# nixie_2020_mainboard_v3_7digit.net
KiCad netlist of a schematic drawn in EAGLE
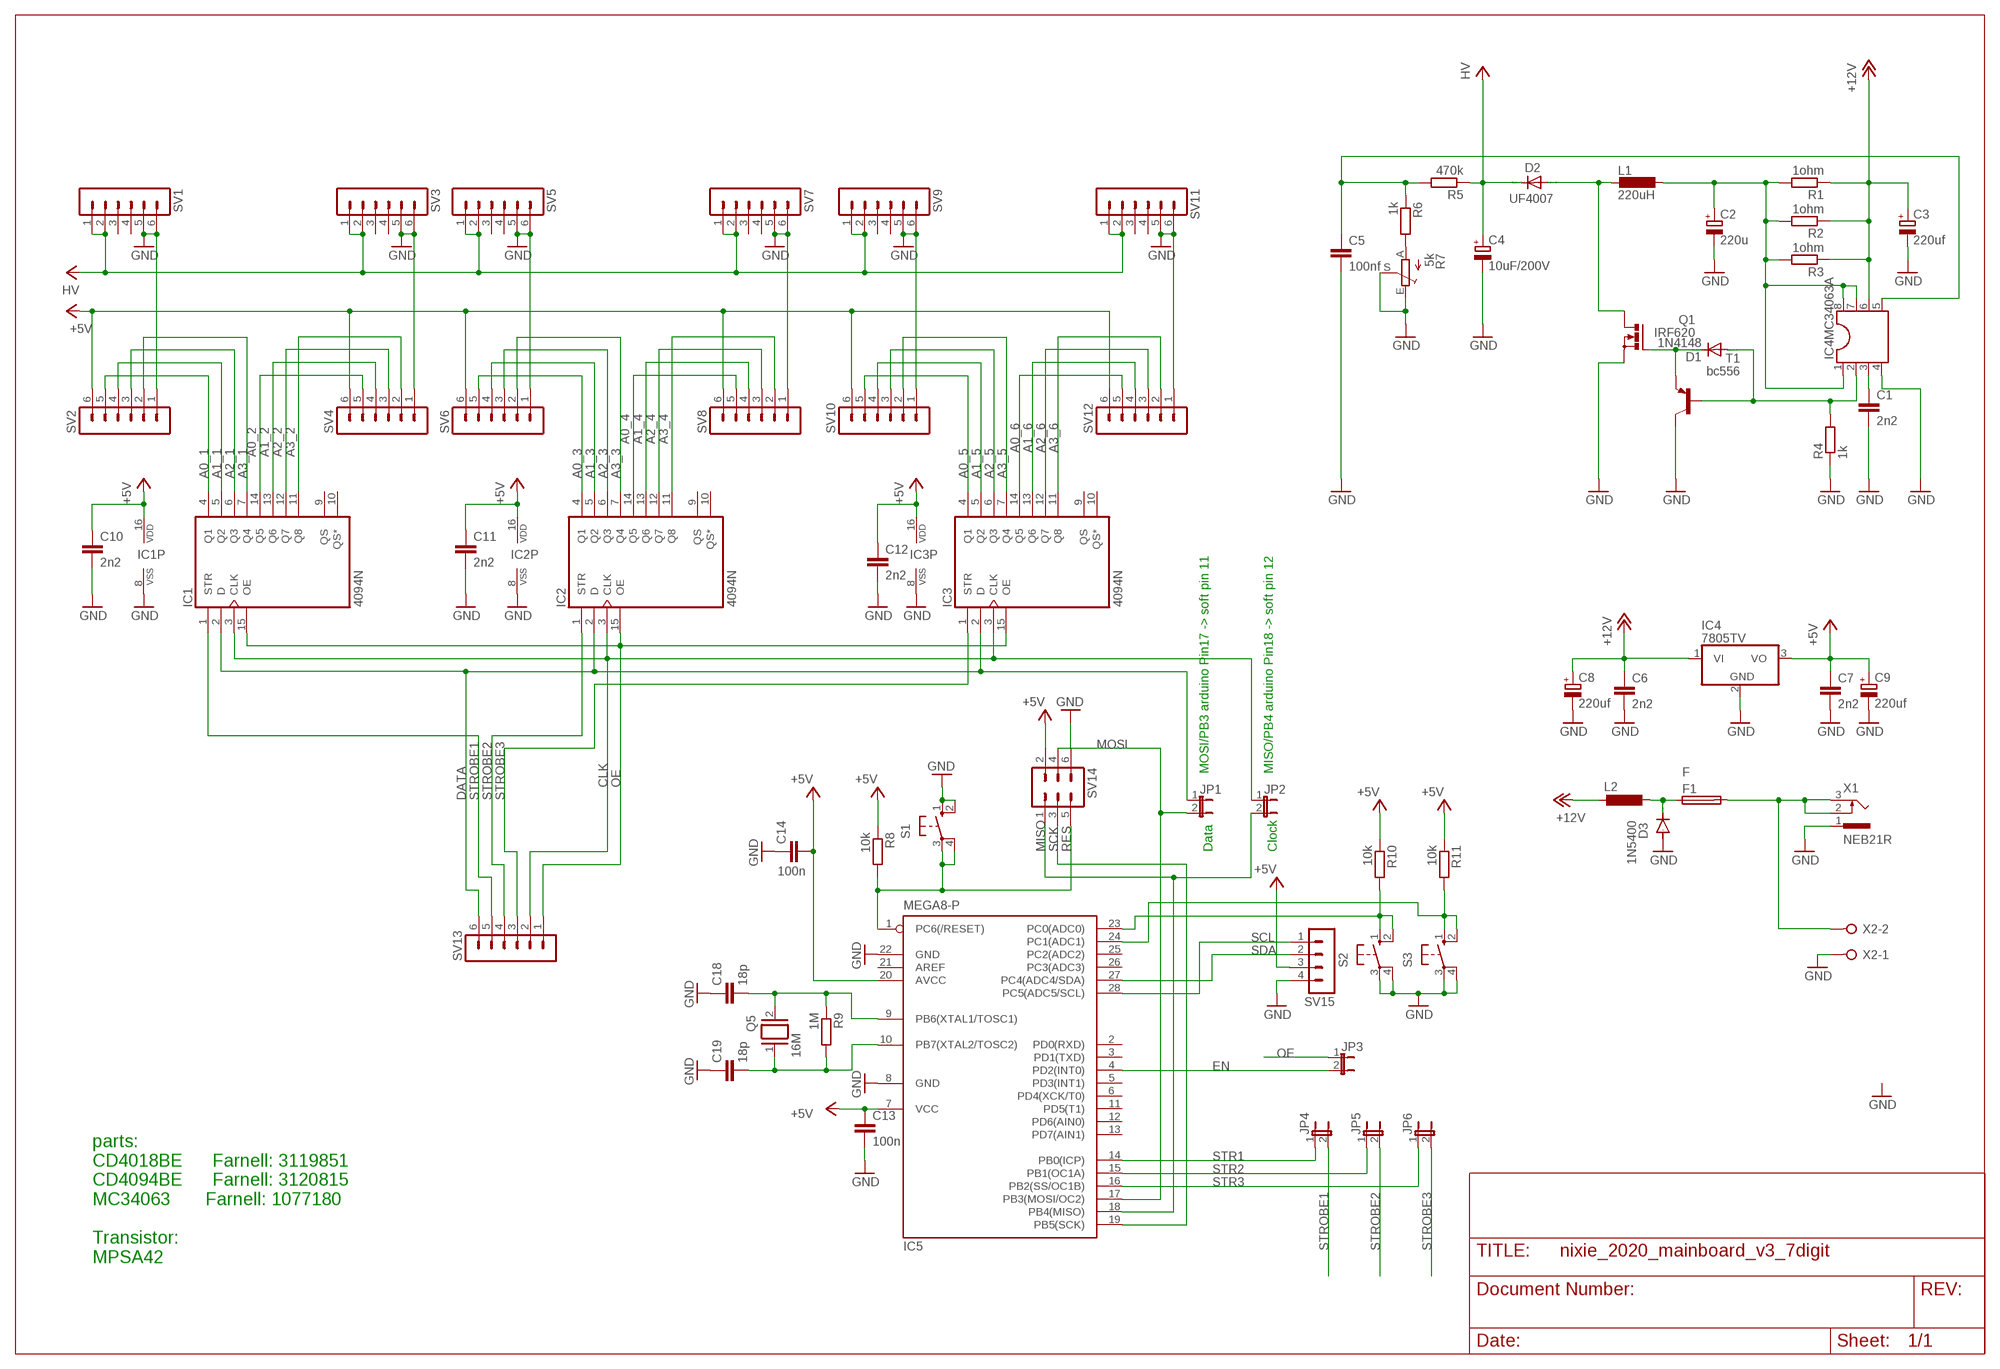
[diagram p0: schematic, sheet 1]

(export (version "E")
  (design (tool "Eeschema 10.0.6"))
  (components
    (comp (ref "C1")
      (value "2n2")
      (footprint "eagle-import:C050-030X075")
      (libsource (lib "eagle-import") (part "C-EU050-030X075"))
    )
    (comp (ref "C2")
      (value "220u")
      (footprint "eagle-import:E5-10,5")
      (libsource (lib "eagle-import") (part "CPOL-EUE5-10.5"))
    )
    (comp (ref "C3")
      (value "220uf")
      (footprint "eagle-import:E5-10,5")
      (libsource (lib "eagle-import") (part "CPOL-EUE5-10.5"))
    )
    (comp (ref "C4")
      (value "10uF/200V")
      (footprint "eagle-import:E5-10,5")
      (libsource (lib "eagle-import") (part "CPOL-EUE5-10.5"))
    )
    (comp (ref "C5")
      (value "100nf")
      (footprint "eagle-import:C075-042X103")
      (libsource (lib "eagle-import") (part "C-EU075-042X103"))
    )
    (comp (ref "C6")
      (value "2n2")
      (footprint "eagle-import:C050-030X075")
      (libsource (lib "eagle-import") (part "C-EU050-030X075"))
    )
    (comp (ref "C7")
      (value "2n2")
      (footprint "eagle-import:C050-030X075")
      (libsource (lib "eagle-import") (part "C-EU050-030X075"))
    )
    (comp (ref "C8")
      (value "220uf")
      (footprint "eagle-import:E5-10,5")
      (libsource (lib "eagle-import") (part "CPOL-EUE5-10.5"))
    )
    (comp (ref "C9")
      (value "220uf")
      (footprint "eagle-import:E5-10,5")
      (libsource (lib "eagle-import") (part "CPOL-EUE5-10.5"))
    )
    (comp (ref "C10")
      (value "2n2")
      (footprint "eagle-import:C050-030X075")
      (libsource (lib "eagle-import") (part "C-EU050-030X075"))
    )
    (comp (ref "C11")
      (value "2n2")
      (footprint "eagle-import:C050-030X075")
      (libsource (lib "eagle-import") (part "C-EU050-030X075"))
    )
    (comp (ref "C12")
      (value "2n2")
      (footprint "eagle-import:C050-030X075")
      (libsource (lib "eagle-import") (part "C-EU050-030X075"))
    )
    (comp (ref "C13")
      (value "100n")
      (footprint "eagle-import:C050-025X075")
      (libsource (lib "eagle-import") (part "resistor_C-EU050-025X075"))
    )
    (comp (ref "C14")
      (value "100n")
      (footprint "eagle-import:C050-025X075")
      (libsource (lib "eagle-import") (part "resistor_C-EU050-025X075"))
    )
    (comp (ref "C18")
      (value "18p")
      (footprint "eagle-import:C050-025X075")
      (libsource (lib "eagle-import") (part "resistor_C-EU050-025X075"))
    )
    (comp (ref "C19")
      (value "18p")
      (footprint "eagle-import:C050-025X075")
      (libsource (lib "eagle-import") (part "resistor_C-EU050-025X075"))
    )
    (comp (ref "D1")
      (value "1N4148")
      (footprint "eagle-import:DO35-10")
      (libsource (lib "eagle-import") (part "1N4148DO35-10"))
    )
    (comp (ref "D2")
      (value "UF4007")
      (footprint "eagle-import:DO35-10")
      (libsource (lib "eagle-import") (part "BAV21"))
    )
    (comp (ref "D3")
      (value "1N5400")
      (footprint "eagle-import:DO201-15")
      (libsource (lib "eagle-import") (part "1N5400"))
    )
    (comp (ref "F1")
      (value "F")
      (footprint "eagle-import:SHK20L")
      (libsource (lib "eagle-import") (part "FUSESHK20L"))
    )
    (comp (ref "IC1")
      (value "4094N")
      (footprint "eagle-import:DIL16")
      (libsource (lib "eagle-import") (part "4094N"))
    )
    (comp (ref "IC2")
      (value "4094N")
      (footprint "eagle-import:DIL16")
      (libsource (lib "eagle-import") (part "4094N"))
    )
    (comp (ref "IC3")
      (value "4094N")
      (footprint "eagle-import:DIL16")
      (libsource (lib "eagle-import") (part "4094N"))
    )
    (comp (ref "IC4")
      (value "7805TV")
      (footprint "eagle-import:TO220V")
      (libsource (lib "eagle-import") (part "78TV05"))
    )
    (comp (ref "IC4MC34063A")
      (value "DIL8S")
      (footprint "eagle-import:SOCKET-08")
      (libsource (lib "eagle-import") (part "DIL8S"))
    )
    (comp (ref "IC5")
      (value "MEGA8-P")
      (footprint "eagle-import:DIL28-3")
      (libsource (lib "eagle-import") (part "MEGA8-P"))
    )
    (comp (ref "JP1")
      (value "JP1E")
      (footprint "eagle-import:JP1")
      (libsource (lib "eagle-import") (part "JP1E"))
    )
    (comp (ref "JP2")
      (value "JP1E")
      (footprint "eagle-import:JP1")
      (libsource (lib "eagle-import") (part "JP1E"))
    )
    (comp (ref "JP3")
      (value "JP1E")
      (footprint "eagle-import:JP1")
      (libsource (lib "eagle-import") (part "JP1E"))
    )
    (comp (ref "JP4")
      (value "JP1E")
      (footprint "eagle-import:JP1")
      (libsource (lib "eagle-import") (part "JP1E"))
    )
    (comp (ref "JP5")
      (value "JP1E")
      (footprint "eagle-import:JP1")
      (libsource (lib "eagle-import") (part "JP1E"))
    )
    (comp (ref "JP6")
      (value "JP1E")
      (footprint "eagle-import:JP1")
      (libsource (lib "eagle-import") (part "JP1E"))
    )
    (comp (ref "L1")
      (value "220uH")
      (footprint "eagle-import:LAN02KR")
      (libsource (lib "eagle-import") (part "L-EULAN02KR"))
    )
    (comp (ref "L2")
      (value "L-EU0207/10")
      (footprint "eagle-import:0207_10")
      (libsource (lib "eagle-import") (part "rcl_334_L-EU0207/10"))
    )
    (comp (ref "Q1")
      (value "IRF620")
      (footprint "eagle-import:TO220BV")
      (libsource (lib "eagle-import") (part "IRF512"))
    )
    (comp (ref "Q5")
      (value "16M")
      (footprint "eagle-import:QS")
      (libsource (lib "eagle-import") (part "XTAL/S"))
    )
    (comp (ref "R1")
      (value "1ohm")
      (footprint "eagle-import:0207_12")
      (libsource (lib "eagle-import") (part "R-EU_0207/12"))
    )
    (comp (ref "R2")
      (value "1ohm")
      (footprint "eagle-import:0207_12")
      (libsource (lib "eagle-import") (part "R-EU_0207/12"))
    )
    (comp (ref "R3")
      (value "1ohm")
      (footprint "eagle-import:0207_12")
      (libsource (lib "eagle-import") (part "R-EU_0207/12"))
    )
    (comp (ref "R4")
      (value "1k")
      (footprint "eagle-import:0207_12")
      (libsource (lib "eagle-import") (part "R-EU_0207/12"))
    )
    (comp (ref "R5")
      (value "470k")
      (footprint "eagle-import:0207_12")
      (libsource (lib "eagle-import") (part "R-EU_0207/12"))
    )
    (comp (ref "R6")
      (value "1k")
      (footprint "eagle-import:0207_12")
      (libsource (lib "eagle-import") (part "R-EU_0207/12"))
    )
    (comp (ref "R7")
      (value "5k")
      (footprint "eagle-import:RJ9W")
      (libsource (lib "eagle-import") (part "TRIM_EU-RJ9W"))
    )
    (comp (ref "R8")
      (value "10k")
      (footprint "eagle-import:0207_12")
      (libsource (lib "eagle-import") (part "R-EU_0207/12"))
    )
    (comp (ref "R9")
      (value "1M")
      (footprint "eagle-import:0207_12")
      (libsource (lib "eagle-import") (part "R-EU_0207/12"))
    )
    (comp (ref "R10")
      (value "10k")
      (footprint "eagle-import:0207_12")
      (libsource (lib "eagle-import") (part "R-EU_0207/12"))
    )
    (comp (ref "R11")
      (value "10k")
      (footprint "eagle-import:0207_12")
      (libsource (lib "eagle-import") (part "R-EU_0207/12"))
    )
    (comp (ref "S1")
      (value "10-XX")
      (footprint "eagle-import:B3F-10XX")
      (fields (field (name "MPN") "B3F-1000"))
      (libsource (lib "eagle-import") (part "10-XX"))
    )
    (comp (ref "S2")
      (value "10-XX")
      (footprint "eagle-import:B3F-10XX")
      (fields (field (name "MPN") "B3F-1000"))
      (libsource (lib "eagle-import") (part "10-XX"))
    )
    (comp (ref "S3")
      (value "10-XX")
      (footprint "eagle-import:B3F-10XX")
      (fields (field (name "MPN") "B3F-1000"))
      (libsource (lib "eagle-import") (part "10-XX"))
    )
    (comp (ref "SV1")
      (value "MA06-1")
      (footprint "eagle-import:MA06-1")
      (libsource (lib "eagle-import") (part "MA06-1"))
    )
    (comp (ref "SV2")
      (value "MA06-1")
      (footprint "eagle-import:MA06-1")
      (libsource (lib "eagle-import") (part "MA06-1"))
    )
    (comp (ref "SV3")
      (value "MA06-1")
      (footprint "eagle-import:MA06-1")
      (libsource (lib "eagle-import") (part "MA06-1"))
    )
    (comp (ref "SV4")
      (value "MA06-1")
      (footprint "eagle-import:MA06-1")
      (libsource (lib "eagle-import") (part "MA06-1"))
    )
    (comp (ref "SV5")
      (value "MA06-1")
      (footprint "eagle-import:MA06-1")
      (libsource (lib "eagle-import") (part "MA06-1"))
    )
    (comp (ref "SV6")
      (value "MA06-1")
      (footprint "eagle-import:MA06-1")
      (libsource (lib "eagle-import") (part "MA06-1"))
    )
    (comp (ref "SV7")
      (value "MA06-1")
      (footprint "eagle-import:MA06-1")
      (libsource (lib "eagle-import") (part "MA06-1"))
    )
    (comp (ref "SV8")
      (value "MA06-1")
      (footprint "eagle-import:MA06-1")
      (libsource (lib "eagle-import") (part "MA06-1"))
    )
    (comp (ref "SV9")
      (value "MA06-1")
      (footprint "eagle-import:MA06-1")
      (libsource (lib "eagle-import") (part "MA06-1"))
    )
    (comp (ref "SV10")
      (value "MA06-1")
      (footprint "eagle-import:MA06-1")
      (libsource (lib "eagle-import") (part "MA06-1"))
    )
    (comp (ref "SV11")
      (value "MA06-1")
      (footprint "eagle-import:MA06-1")
      (libsource (lib "eagle-import") (part "MA06-1"))
    )
    (comp (ref "SV12")
      (value "MA06-1")
      (footprint "eagle-import:MA06-1")
      (libsource (lib "eagle-import") (part "MA06-1"))
    )
    (comp (ref "SV13")
      (value "MA06-1")
      (footprint "eagle-import:MA06-1")
      (libsource (lib "eagle-import") (part "MA06-1"))
    )
    (comp (ref "SV14")
      (value "MA03-2")
      (footprint "eagle-import:MA03-2")
      (libsource (lib "eagle-import") (part "MA03-2"))
    )
    (comp (ref "SV15")
      (value "MA04-1")
      (footprint "eagle-import:MA04-1")
      (libsource (lib "eagle-import") (part "MA04-1"))
    )
    (comp (ref "T1")
      (value "bc556")
      (footprint "eagle-import:TO92-EBC")
      (libsource (lib "eagle-import") (part "-PNP-TO92-EBCBC556A"))
    )
    (comp (ref "X1")
      (value "NEB21R")
      (footprint "eagle-import:NEB21R")
      (fields (field (name "MPN") "NEB 21 R"))
      (libsource (lib "eagle-import") (part "NEB21R"))
    )
    (comp (ref "X2")
      (value "W237-02P")
      (footprint "eagle-import:W237-132")
      (libsource (lib "eagle-import") (part "W237-02P"))
    )
  )
  (nets
    (net (code "1") (name "+5V") (class "Default")
      (node (ref "C10") (pin "1") (pinfunction "1_1") (pintype "passive"))
      (node (ref "C11") (pin "1") (pinfunction "1_1") (pintype "passive"))
      (node (ref "C12") (pin "1") (pinfunction "1_1") (pintype "passive"))
      (node (ref "C13") (pin "1") (pinfunction "1_1") (pintype "passive"))
      (node (ref "C14") (pin "2") (pinfunction "2_2") (pintype "passive"))
      (node (ref "C7") (pin "1") (pinfunction "1_1") (pintype "passive"))
      (node (ref "C9") (pin "+") (pinfunction "+_+") (pintype "passive"))
      (node (ref "IC1") (pin "16") (pinfunction "VDD_16") (pintype "power_in"))
      (node (ref "IC2") (pin "16") (pinfunction "VDD_16") (pintype "power_in"))
      (node (ref "IC3") (pin "16") (pinfunction "VDD_16") (pintype "power_in"))
      (node (ref "IC4") (pin "3") (pinfunction "VO_3") (pintype "passive"))
      (node (ref "IC5") (pin "20") (pinfunction "AVCC_20") (pintype "power_in"))
      (node (ref "IC5") (pin "7") (pinfunction "VCC_7") (pintype "power_in"))
      (node (ref "R10") (pin "1") (pinfunction "1_1") (pintype "passive"))
      (node (ref "R11") (pin "1") (pinfunction "1_1") (pintype "passive"))
      (node (ref "R8") (pin "1") (pinfunction "1_1") (pintype "passive"))
      (node (ref "SV10") (pin "6") (pinfunction "6_6") (pintype "passive"))
      (node (ref "SV12") (pin "6") (pinfunction "6_6") (pintype "passive"))
      (node (ref "SV14") (pin "2") (pinfunction "2_2") (pintype "passive"))
      (node (ref "SV15") (pin "3") (pinfunction "3_3") (pintype "passive"))
      (node (ref "SV2") (pin "6") (pinfunction "6_6") (pintype "passive"))
      (node (ref "SV4") (pin "6") (pinfunction "6_6") (pintype "passive"))
      (node (ref "SV6") (pin "6") (pinfunction "6_6") (pintype "passive"))
      (node (ref "SV8") (pin "6") (pinfunction "6_6") (pintype "passive"))
    )
    (net (code "2") (name "+12V") (class "Default")
      (node (ref "C3") (pin "+") (pinfunction "+_+") (pintype "passive"))
      (node (ref "C6") (pin "1") (pinfunction "1_1") (pintype "passive"))
      (node (ref "C8") (pin "+") (pinfunction "+_+") (pintype "passive"))
      (node (ref "IC4") (pin "1") (pinfunction "VI_1") (pintype "input"))
      (node (ref "IC4MC34063A") (pin "6") (pinfunction "6_6") (pintype "passive"))
      (node (ref "L2") (pin "1") (pinfunction "1_1") (pintype "passive"))
      (node (ref "R1") (pin "1") (pinfunction "1_1") (pintype "passive"))
      (node (ref "R2") (pin "1") (pinfunction "1_1") (pintype "passive"))
      (node (ref "R3") (pin "1") (pinfunction "1_1") (pintype "passive"))
    )
    (net (code "3") (name "/A0_1") (class "Default")
      (node (ref "IC1") (pin "4") (pinfunction "Q1_4") (pintype "output"))
      (node (ref "SV2") (pin "5") (pinfunction "5_5") (pintype "passive"))
    )
    (net (code "4") (name "/A0_2") (class "Default")
      (node (ref "IC1") (pin "14") (pinfunction "Q5_14") (pintype "output"))
      (node (ref "SV4") (pin "5") (pinfunction "5_5") (pintype "passive"))
    )
    (net (code "5") (name "/A0_3") (class "Default")
      (node (ref "IC2") (pin "4") (pinfunction "Q1_4") (pintype "output"))
      (node (ref "SV6") (pin "5") (pinfunction "5_5") (pintype "passive"))
    )
    (net (code "6") (name "/A0_4") (class "Default")
      (node (ref "IC2") (pin "14") (pinfunction "Q5_14") (pintype "output"))
      (node (ref "SV8") (pin "5") (pinfunction "5_5") (pintype "passive"))
    )
    (net (code "7") (name "/A0_5") (class "Default")
      (node (ref "IC3") (pin "4") (pinfunction "Q1_4") (pintype "output"))
      (node (ref "SV10") (pin "5") (pinfunction "5_5") (pintype "passive"))
    )
    (net (code "8") (name "/A0_6") (class "Default")
      (node (ref "IC3") (pin "14") (pinfunction "Q5_14") (pintype "output"))
      (node (ref "SV12") (pin "5") (pinfunction "5_5") (pintype "passive"))
    )
    (net (code "9") (name "/A1_1") (class "Default")
      (node (ref "IC1") (pin "5") (pinfunction "Q2_5") (pintype "output"))
      (node (ref "SV2") (pin "4") (pinfunction "4_4") (pintype "passive"))
    )
    (net (code "10") (name "/A1_2") (class "Default")
      (node (ref "IC1") (pin "13") (pinfunction "Q6_13") (pintype "output"))
      (node (ref "SV4") (pin "4") (pinfunction "4_4") (pintype "passive"))
    )
    (net (code "11") (name "/A1_3") (class "Default")
      (node (ref "IC2") (pin "5") (pinfunction "Q2_5") (pintype "output"))
      (node (ref "SV6") (pin "4") (pinfunction "4_4") (pintype "passive"))
    )
    (net (code "12") (name "/A1_4") (class "Default")
      (node (ref "IC2") (pin "13") (pinfunction "Q6_13") (pintype "output"))
      (node (ref "SV8") (pin "4") (pinfunction "4_4") (pintype "passive"))
    )
    (net (code "13") (name "/A1_5") (class "Default")
      (node (ref "IC3") (pin "5") (pinfunction "Q2_5") (pintype "output"))
      (node (ref "SV10") (pin "4") (pinfunction "4_4") (pintype "passive"))
    )
    (net (code "14") (name "/A1_6") (class "Default")
      (node (ref "IC3") (pin "13") (pinfunction "Q6_13") (pintype "output"))
      (node (ref "SV12") (pin "4") (pinfunction "4_4") (pintype "passive"))
    )
    (net (code "15") (name "/A2_1") (class "Default")
      (node (ref "IC1") (pin "6") (pinfunction "Q3_6") (pintype "output"))
      (node (ref "SV2") (pin "3") (pinfunction "3_3") (pintype "passive"))
    )
    (net (code "16") (name "/A2_2") (class "Default")
      (node (ref "IC1") (pin "12") (pinfunction "Q7_12") (pintype "output"))
      (node (ref "SV4") (pin "3") (pinfunction "3_3") (pintype "passive"))
    )
    (net (code "17") (name "/A2_3") (class "Default")
      (node (ref "IC2") (pin "6") (pinfunction "Q3_6") (pintype "output"))
      (node (ref "SV6") (pin "3") (pinfunction "3_3") (pintype "passive"))
    )
    (net (code "18") (name "/A2_4") (class "Default")
      (node (ref "IC2") (pin "12") (pinfunction "Q7_12") (pintype "output"))
      (node (ref "SV8") (pin "3") (pinfunction "3_3") (pintype "passive"))
    )
    (net (code "19") (name "/A2_5") (class "Default")
      (node (ref "IC3") (pin "6") (pinfunction "Q3_6") (pintype "output"))
      (node (ref "SV10") (pin "3") (pinfunction "3_3") (pintype "passive"))
    )
    (net (code "20") (name "/A2_6") (class "Default")
      (node (ref "IC3") (pin "12") (pinfunction "Q7_12") (pintype "output"))
      (node (ref "SV12") (pin "3") (pinfunction "3_3") (pintype "passive"))
    )
    (net (code "21") (name "/A3_1") (class "Default")
      (node (ref "IC1") (pin "7") (pinfunction "Q4_7") (pintype "output"))
      (node (ref "SV2") (pin "2") (pinfunction "2_2") (pintype "passive"))
    )
    (net (code "22") (name "/A3_2") (class "Default")
      (node (ref "IC1") (pin "11") (pinfunction "Q8_11") (pintype "output"))
      (node (ref "SV4") (pin "2") (pinfunction "2_2") (pintype "passive"))
    )
    (net (code "23") (name "/A3_3") (class "Default")
      (node (ref "IC2") (pin "7") (pinfunction "Q4_7") (pintype "output"))
      (node (ref "SV6") (pin "2") (pinfunction "2_2") (pintype "passive"))
    )
    (net (code "24") (name "/A3_4") (class "Default")
      (node (ref "IC2") (pin "11") (pinfunction "Q8_11") (pintype "output"))
      (node (ref "SV8") (pin "2") (pinfunction "2_2") (pintype "passive"))
    )
    (net (code "25") (name "/A3_5") (class "Default")
      (node (ref "IC3") (pin "7") (pinfunction "Q4_7") (pintype "output"))
      (node (ref "SV10") (pin "2") (pinfunction "2_2") (pintype "passive"))
    )
    (net (code "26") (name "/A3_6") (class "Default")
      (node (ref "IC3") (pin "11") (pinfunction "Q8_11") (pintype "output"))
      (node (ref "SV12") (pin "2") (pinfunction "2_2") (pintype "passive"))
    )
    (net (code "27") (name "/CLK") (class "Default")
      (node (ref "IC1") (pin "3") (pinfunction "CLK_3") (pintype "input"))
      (node (ref "IC2") (pin "3") (pinfunction "CLK_3") (pintype "input"))
      (node (ref "IC3") (pin "3") (pinfunction "CLK_3") (pintype "input"))
      (node (ref "JP2") (pin "1") (pinfunction "1_1") (pintype "passive"))
      (node (ref "SV13") (pin "2") (pinfunction "2_2") (pintype "passive"))
    )
    (net (code "28") (name "/DATA") (class "Default")
      (node (ref "IC1") (pin "2") (pinfunction "D_2") (pintype "input"))
      (node (ref "IC2") (pin "2") (pinfunction "D_2") (pintype "input"))
      (node (ref "IC3") (pin "2") (pinfunction "D_2") (pintype "input"))
      (node (ref "JP1") (pin "1") (pinfunction "1_1") (pintype "passive"))
      (node (ref "SV13") (pin "6") (pinfunction "6_6") (pintype "passive"))
    )
    (net (code "29") (name "/EN") (class "Default")
      (node (ref "IC5") (pin "4") (pinfunction "PD2(INT0)_4") (pintype "bidirectional"))
      (node (ref "JP3") (pin "2") (pinfunction "2_2") (pintype "passive"))
    )
    (net (code "30") (name "/MISO") (class "Default")
      (node (ref "IC5") (pin "18") (pinfunction "PB4(MISO)_18") (pintype "bidirectional"))
      (node (ref "JP2") (pin "2") (pinfunction "2_2") (pintype "passive"))
      (node (ref "SV14") (pin "1") (pinfunction "1_1") (pintype "passive"))
    )
    (net (code "31") (name "/MOSI") (class "Default")
      (node (ref "IC5") (pin "17") (pinfunction "PB3(MOSI/OC2)_17") (pintype "bidirectional"))
      (node (ref "JP1") (pin "2") (pinfunction "2_2") (pintype "passive"))
      (node (ref "SV14") (pin "4") (pinfunction "4_4") (pintype "passive"))
    )
    (net (code "32") (name "/OE") (class "Default")
      (node (ref "IC1") (pin "15") (pinfunction "OE_15") (pintype "input"))
      (node (ref "IC2") (pin "15") (pinfunction "OE_15") (pintype "input"))
      (node (ref "IC3") (pin "15") (pinfunction "OE_15") (pintype "input"))
      (node (ref "JP3") (pin "1") (pinfunction "1_1") (pintype "passive"))
      (node (ref "SV13") (pin "1") (pinfunction "1_1") (pintype "passive"))
    )
    (net (code "33") (name "/RES") (class "Default")
      (node (ref "IC5") (pin "1") (pinfunction "PC6(/RESET)_1") (pintype "bidirectional"))
      (node (ref "R8") (pin "2") (pinfunction "2_2") (pintype "passive"))
      (node (ref "S1") (pin "3") (pinfunction "P_3") (pintype "passive"))
      (node (ref "S1") (pin "4") (pinfunction "P1_4") (pintype "passive"))
      (node (ref "SV14") (pin "5") (pinfunction "5_5") (pintype "passive"))
    )
    (net (code "34") (name "/SCK") (class "Default")
      (node (ref "IC5") (pin "19") (pinfunction "PB5(SCK)_19") (pintype "bidirectional"))
      (node (ref "SV14") (pin "3") (pinfunction "3_3") (pintype "passive"))
    )
    (net (code "35") (name "/SCL") (class "Default")
      (node (ref "IC5") (pin "28") (pinfunction "PC5(ADC5/SCL)_28") (pintype "bidirectional"))
      (node (ref "SV15") (pin "1") (pinfunction "1_1") (pintype "passive"))
    )
    (net (code "36") (name "/SDA") (class "Default")
      (node (ref "IC5") (pin "27") (pinfunction "PC4(ADC4/SDA)_27") (pintype "bidirectional"))
      (node (ref "SV15") (pin "2") (pinfunction "2_2") (pintype "passive"))
    )
    (net (code "37") (name "/STR1") (class "Default")
      (node (ref "IC5") (pin "14") (pinfunction "PB0(ICP)_14") (pintype "bidirectional"))
      (node (ref "JP4") (pin "1") (pinfunction "1_1") (pintype "passive"))
    )
    (net (code "38") (name "/STR2") (class "Default")
      (node (ref "IC5") (pin "15") (pinfunction "PB1(OC1A)_15") (pintype "bidirectional"))
      (node (ref "JP5") (pin "1") (pinfunction "1_1") (pintype "passive"))
    )
    (net (code "39") (name "/STR3") (class "Default")
      (node (ref "IC5") (pin "16") (pinfunction "PB2(SS/OC1B)_16") (pintype "bidirectional"))
      (node (ref "JP6") (pin "1") (pinfunction "1_1") (pintype "passive"))
    )
    (net (code "40") (name "/STROBE1") (class "Default")
      (node (ref "IC1") (pin "1") (pinfunction "STR_1") (pintype "input"))
      (node (ref "JP4") (pin "2") (pinfunction "2_2") (pintype "passive"))
      (node (ref "SV13") (pin "5") (pinfunction "5_5") (pintype "passive"))
    )
    (net (code "41") (name "/STROBE2") (class "Default")
      (node (ref "IC2") (pin "1") (pinfunction "STR_1") (pintype "input"))
      (node (ref "JP5") (pin "2") (pinfunction "2_2") (pintype "passive"))
      (node (ref "SV13") (pin "4") (pinfunction "4_4") (pintype "passive"))
    )
    (net (code "42") (name "/STROBE3") (class "Default")
      (node (ref "IC3") (pin "1") (pinfunction "STR_1") (pintype "input"))
      (node (ref "JP6") (pin "2") (pinfunction "2_2") (pintype "passive"))
      (node (ref "SV13") (pin "3") (pinfunction "3_3") (pintype "passive"))
    )
    (net (code "43") (name "GND") (class "Default")
      (node (ref "C1") (pin "2") (pinfunction "2_2") (pintype "passive"))
      (node (ref "C10") (pin "2") (pinfunction "2_2") (pintype "passive"))
      (node (ref "C11") (pin "2") (pinfunction "2_2") (pintype "passive"))
      (node (ref "C12") (pin "2") (pinfunction "2_2") (pintype "passive"))
      (node (ref "C13") (pin "2") (pinfunction "2_2") (pintype "passive"))
      (node (ref "C14") (pin "1") (pinfunction "1_1") (pintype "passive"))
      (node (ref "C18") (pin "1") (pinfunction "1_1") (pintype "passive"))
      (node (ref "C19") (pin "1") (pinfunction "1_1") (pintype "passive"))
      (node (ref "C2") (pin "-") (pinfunction "-_-") (pintype "passive"))
      (node (ref "C3") (pin "-") (pinfunction "-_-") (pintype "passive"))
      (node (ref "C4") (pin "-") (pinfunction "-_-") (pintype "passive"))
      (node (ref "C5") (pin "2") (pinfunction "2_2") (pintype "passive"))
      (node (ref "C6") (pin "2") (pinfunction "2_2") (pintype "passive"))
      (node (ref "C7") (pin "2") (pinfunction "2_2") (pintype "passive"))
      (node (ref "C8") (pin "-") (pinfunction "-_-") (pintype "passive"))
      (node (ref "C9") (pin "-") (pinfunction "-_-") (pintype "passive"))
      (node (ref "D3") (pin "A") (pinfunction "A_A") (pintype "passive"))
      (node (ref "IC1") (pin "8") (pinfunction "VSS_8") (pintype "power_in"))
      (node (ref "IC2") (pin "8") (pinfunction "VSS_8") (pintype "power_in"))
      (node (ref "IC3") (pin "8") (pinfunction "VSS_8") (pintype "power_in"))
      (node (ref "IC4") (pin "2") (pinfunction "GND_2") (pintype "passive"))
      (node (ref "IC4MC34063A") (pin "4") (pinfunction "4_4") (pintype "passive"))
      (node (ref "IC5") (pin "22") (pinfunction "GND_22") (pintype "power_in"))
      (node (ref "IC5") (pin "8") (pinfunction "GND_8") (pintype "power_in"))
      (node (ref "Q1") (pin "S") (pinfunction "S_S") (pintype "passive"))
      (node (ref "R4") (pin "1") (pinfunction "1_1") (pintype "passive"))
      (node (ref "R7") (pin "E") (pinfunction "E_E") (pintype "passive"))
      (node (ref "R7") (pin "S") (pinfunction "S_S") (pintype "passive"))
      (node (ref "S1") (pin "1") (pinfunction "S_1") (pintype "passive"))
      (node (ref "S1") (pin "2") (pinfunction "S1_2") (pintype "passive"))
      (node (ref "S2") (pin "3") (pinfunction "P_3") (pintype "passive"))
      (node (ref "S2") (pin "4") (pinfunction "P1_4") (pintype "passive"))
      (node (ref "S3") (pin "3") (pinfunction "P_3") (pintype "passive"))
      (node (ref "S3") (pin "4") (pinfunction "P1_4") (pintype "passive"))
      (node (ref "SV1") (pin "5") (pinfunction "5_5") (pintype "passive"))
      (node (ref "SV1") (pin "6") (pinfunction "6_6") (pintype "passive"))
      (node (ref "SV10") (pin "1") (pinfunction "1_1") (pintype "passive"))
      (node (ref "SV11") (pin "5") (pinfunction "5_5") (pintype "passive"))
      (node (ref "SV11") (pin "6") (pinfunction "6_6") (pintype "passive"))
      (node (ref "SV12") (pin "1") (pinfunction "1_1") (pintype "passive"))
      (node (ref "SV14") (pin "6") (pinfunction "6_6") (pintype "passive"))
      (node (ref "SV15") (pin "4") (pinfunction "4_4") (pintype "passive"))
      (node (ref "SV2") (pin "1") (pinfunction "1_1") (pintype "passive"))
      (node (ref "SV3") (pin "5") (pinfunction "5_5") (pintype "passive"))
      (node (ref "SV3") (pin "6") (pinfunction "6_6") (pintype "passive"))
      (node (ref "SV4") (pin "1") (pinfunction "1_1") (pintype "passive"))
      (node (ref "SV5") (pin "5") (pinfunction "5_5") (pintype "passive"))
      (node (ref "SV5") (pin "6") (pinfunction "6_6") (pintype "passive"))
      (node (ref "SV6") (pin "1") (pinfunction "1_1") (pintype "passive"))
      (node (ref "SV7") (pin "5") (pinfunction "5_5") (pintype "passive"))
      (node (ref "SV7") (pin "6") (pinfunction "6_6") (pintype "passive"))
      (node (ref "SV8") (pin "1") (pinfunction "1_1") (pintype "passive"))
      (node (ref "SV9") (pin "5") (pinfunction "5_5") (pintype "passive"))
      (node (ref "SV9") (pin "6") (pinfunction "6_6") (pintype "passive"))
      (node (ref "T1") (pin "C") (pinfunction "C_C") (pintype "passive"))
      (node (ref "X1") (pin "1") (pinfunction "1_1") (pintype "passive"))
      (node (ref "X2") (pin "1") (pinfunction "KL_1") (pintype "passive"))
    )
    (net (code "44") (name "HV") (class "Default")
      (node (ref "C4") (pin "+") (pinfunction "+_+") (pintype "passive"))
      (node (ref "D2") (pin "C") (pinfunction "C_C") (pintype "passive"))
      (node (ref "R5") (pin "1") (pinfunction "1_1") (pintype "passive"))
      (node (ref "SV1") (pin "1") (pinfunction "1_1") (pintype "passive"))
      (node (ref "SV1") (pin "2") (pinfunction "2_2") (pintype "passive"))
      (node (ref "SV11") (pin "1") (pinfunction "1_1") (pintype "passive"))
      (node (ref "SV11") (pin "2") (pinfunction "2_2") (pintype "passive"))
      (node (ref "SV3") (pin "1") (pinfunction "1_1") (pintype "passive"))
      (node (ref "SV3") (pin "2") (pinfunction "2_2") (pintype "passive"))
      (node (ref "SV5") (pin "1") (pinfunction "1_1") (pintype "passive"))
      (node (ref "SV5") (pin "2") (pinfunction "2_2") (pintype "passive"))
      (node (ref "SV7") (pin "1") (pinfunction "1_1") (pintype "passive"))
      (node (ref "SV7") (pin "2") (pinfunction "2_2") (pintype "passive"))
      (node (ref "SV9") (pin "1") (pinfunction "1_1") (pintype "passive"))
      (node (ref "SV9") (pin "2") (pinfunction "2_2") (pintype "passive"))
    )
    (net (code "45") (name "Net-(C1-Pad1)") (class "Default")
      (node (ref "C1") (pin "1") (pinfunction "1_1") (pintype "passive"))
      (node (ref "IC4MC34063A") (pin "3") (pinfunction "3_3") (pintype "passive"))
    )
    (net (code "46") (name "Net-(C2-Pad+)") (class "Default")
      (node (ref "C2") (pin "+") (pinfunction "+_+") (pintype "passive"))
      (node (ref "IC4MC34063A") (pin "1") (pinfunction "1_1") (pintype "passive"))
      (node (ref "IC4MC34063A") (pin "7") (pinfunction "7_7") (pintype "passive"))
      (node (ref "IC4MC34063A") (pin "8") (pinfunction "8_8") (pintype "passive"))
      (node (ref "L1") (pin "1") (pinfunction "1_1") (pintype "passive"))
      (node (ref "R1") (pin "2") (pinfunction "2_2") (pintype "passive"))
      (node (ref "R2") (pin "2") (pinfunction "2_2") (pintype "passive"))
      (node (ref "R3") (pin "2") (pinfunction "2_2") (pintype "passive"))
    )
    (net (code "47") (name "Net-(C5-Pad1)") (class "Default")
      (node (ref "C5") (pin "1") (pinfunction "1_1") (pintype "passive"))
      (node (ref "IC4MC34063A") (pin "5") (pinfunction "5_5") (pintype "passive"))
      (node (ref "R5") (pin "2") (pinfunction "2_2") (pintype "passive"))
      (node (ref "R6") (pin "1") (pinfunction "1_1") (pintype "passive"))
    )
    (net (code "48") (name "Net-(D1-PadA)") (class "Default")
      (node (ref "D1") (pin "A") (pinfunction "A_A") (pintype "passive"))
      (node (ref "IC4MC34063A") (pin "2") (pinfunction "2_2") (pintype "passive"))
      (node (ref "R4") (pin "2") (pinfunction "2_2") (pintype "passive"))
      (node (ref "T1") (pin "B") (pinfunction "B_B") (pintype "passive"))
    )
    (net (code "49") (name "Net-(D1-PadC)") (class "Default")
      (node (ref "D1") (pin "C") (pinfunction "C_C") (pintype "passive"))
      (node (ref "Q1") (pin "G") (pinfunction "G_G") (pintype "passive"))
      (node (ref "T1") (pin "E") (pinfunction "E_E") (pintype "passive"))
    )
    (net (code "50") (name "Net-(D2-PadA)") (class "Default")
      (node (ref "D2") (pin "A") (pinfunction "A_A") (pintype "passive"))
      (node (ref "L1") (pin "2") (pinfunction "2_2") (pintype "passive"))
      (node (ref "Q1") (pin "D") (pinfunction "D_D") (pintype "passive"))
    )
    (net (code "51") (name "Net-(F1-1)") (class "Default")
      (node (ref "D3") (pin "C") (pinfunction "C_C") (pintype "passive"))
      (node (ref "F1") (pin "1A") (pinfunction "1_1A") (pintype "passive"))
      (node (ref "L2") (pin "2") (pinfunction "2_2") (pintype "passive"))
    )
    (net (code "52") (name "Net-(F1-2)") (class "Default")
      (node (ref "F1") (pin "2A") (pinfunction "2_2A") (pintype "passive"))
      (node (ref "X1") (pin "2") (pinfunction "2_2") (pintype "passive"))
      (node (ref "X1") (pin "3") (pinfunction "3_3") (pintype "passive"))
      (node (ref "X2") (pin "2") (pinfunction "KL_2") (pintype "passive"))
    )
    (net (code "53") (name "Net-(IC5-PB6(XTAL1{slash}TOSC1))") (class "Default")
      (node (ref "C18") (pin "2") (pinfunction "2_2") (pintype "passive"))
      (node (ref "IC5") (pin "9") (pinfunction "PB6(XTAL1/TOSC1)_9") (pintype "bidirectional"))
      (node (ref "Q5") (pin "2") (pinfunction "2_2") (pintype "passive"))
      (node (ref "R9") (pin "1") (pinfunction "1_1") (pintype "passive"))
    )
    (net (code "54") (name "Net-(IC5-PB7(XTAL2{slash}TOSC2))") (class "Default")
      (node (ref "C19") (pin "2") (pinfunction "2_2") (pintype "passive"))
      (node (ref "IC5") (pin "10") (pinfunction "PB7(XTAL2/TOSC2)_10") (pintype "bidirectional"))
      (node (ref "Q5") (pin "1") (pinfunction "1_1") (pintype "passive"))
      (node (ref "R9") (pin "2") (pinfunction "2_2") (pintype "passive"))
    )
    (net (code "55") (name "Net-(IC5-PC0(ADC0))") (class "Default")
      (node (ref "IC5") (pin "23") (pinfunction "PC0(ADC0)_23") (pintype "bidirectional"))
      (node (ref "R10") (pin "2") (pinfunction "2_2") (pintype "passive"))
      (node (ref "S2") (pin "1") (pinfunction "S_1") (pintype "passive"))
      (node (ref "S2") (pin "2") (pinfunction "S1_2") (pintype "passive"))
    )
    (net (code "56") (name "Net-(IC5-PC1(ADC1))") (class "Default")
      (node (ref "IC5") (pin "24") (pinfunction "PC1(ADC1)_24") (pintype "bidirectional"))
      (node (ref "R11") (pin "2") (pinfunction "2_2") (pintype "passive"))
      (node (ref "S3") (pin "1") (pinfunction "S_1") (pintype "passive"))
      (node (ref "S3") (pin "2") (pinfunction "S1_2") (pintype "passive"))
    )
    (net (code "57") (name "Net-(R6-Pad2)") (class "Default")
      (node (ref "R6") (pin "2") (pinfunction "2_2") (pintype "passive"))
      (node (ref "R7") (pin "A") (pinfunction "A_A") (pintype "passive"))
    )
    (net (code "58") (name "unconnected-(IC1A-QS*-Pad10)") (class "Default")
      (node (ref "IC1") (pin "10") (pinfunction "QS*_10") (pintype "output"))
    )
    (net (code "59") (name "unconnected-(IC1A-QS-Pad9)") (class "Default")
      (node (ref "IC1") (pin "9") (pinfunction "QS_9") (pintype "output"))
    )
    (net (code "60") (name "unconnected-(IC2A-QS*-Pad10)") (class "Default")
      (node (ref "IC2") (pin "10") (pinfunction "QS*_10") (pintype "output"))
    )
    (net (code "61") (name "unconnected-(IC2A-QS-Pad9)") (class "Default")
      (node (ref "IC2") (pin "9") (pinfunction "QS_9") (pintype "output"))
    )
    (net (code "62") (name "unconnected-(IC3A-QS*-Pad10)") (class "Default")
      (node (ref "IC3") (pin "10") (pinfunction "QS*_10") (pintype "output"))
    )
    (net (code "63") (name "unconnected-(IC3A-QS-Pad9)") (class "Default")
      (node (ref "IC3") (pin "9") (pinfunction "QS_9") (pintype "output"))
    )
    (net (code "64") (name "unconnected-(IC5-AREF-Pad21)") (class "Default")
      (node (ref "IC5") (pin "21") (pinfunction "AREF_21") (pintype "passive"))
    )
    (net (code "65") (name "unconnected-(IC5-PC2(ADC2)-Pad25)") (class "Default")
      (node (ref "IC5") (pin "25") (pinfunction "PC2(ADC2)_25") (pintype "bidirectional"))
    )
    (net (code "66") (name "unconnected-(IC5-PC3(ADC3)-Pad26)") (class "Default")
      (node (ref "IC5") (pin "26") (pinfunction "PC3(ADC3)_26") (pintype "bidirectional"))
    )
    (net (code "67") (name "unconnected-(IC5-PD0(RXD)-Pad2)") (class "Default")
      (node (ref "IC5") (pin "2") (pinfunction "PD0(RXD)_2") (pintype "bidirectional"))
    )
    (net (code "68") (name "unconnected-(IC5-PD1(TXD)-Pad3)") (class "Default")
      (node (ref "IC5") (pin "3") (pinfunction "PD1(TXD)_3") (pintype "bidirectional"))
    )
    (net (code "69") (name "unconnected-(IC5-PD3(INT1)-Pad5)") (class "Default")
      (node (ref "IC5") (pin "5") (pinfunction "PD3(INT1)_5") (pintype "bidirectional"))
    )
    (net (code "70") (name "unconnected-(IC5-PD4(XCK{slash}T0)-Pad6)") (class "Default")
      (node (ref "IC5") (pin "6") (pinfunction "PD4(XCK/T0)_6") (pintype "bidirectional"))
    )
    (net (code "71") (name "unconnected-(IC5-PD5(T1)-Pad11)") (class "Default")
      (node (ref "IC5") (pin "11") (pinfunction "PD5(T1)_11") (pintype "bidirectional"))
    )
    (net (code "72") (name "unconnected-(IC5-PD6(AIN0)-Pad12)") (class "Default")
      (node (ref "IC5") (pin "12") (pinfunction "PD6(AIN0)_12") (pintype "bidirectional"))
    )
    (net (code "73") (name "unconnected-(IC5-PD7(AIN1)-Pad13)") (class "Default")
      (node (ref "IC5") (pin "13") (pinfunction "PD7(AIN1)_13") (pintype "bidirectional"))
    )
    (net (code "74") (name "unconnected-(SV1-Pad3)") (class "Default")
      (node (ref "SV1") (pin "3") (pinfunction "3_3") (pintype "passive"))
    )
    (net (code "75") (name "unconnected-(SV1-Pad4)") (class "Default")
      (node (ref "SV1") (pin "4") (pinfunction "4_4") (pintype "passive"))
    )
    (net (code "76") (name "unconnected-(SV3-Pad3)") (class "Default")
      (node (ref "SV3") (pin "3") (pinfunction "3_3") (pintype "passive"))
    )
    (net (code "77") (name "unconnected-(SV3-Pad4)") (class "Default")
      (node (ref "SV3") (pin "4") (pinfunction "4_4") (pintype "passive"))
    )
    (net (code "78") (name "unconnected-(SV5-Pad3)") (class "Default")
      (node (ref "SV5") (pin "3") (pinfunction "3_3") (pintype "passive"))
    )
    (net (code "79") (name "unconnected-(SV5-Pad4)") (class "Default")
      (node (ref "SV5") (pin "4") (pinfunction "4_4") (pintype "passive"))
    )
    (net (code "80") (name "unconnected-(SV7-Pad3)") (class "Default")
      (node (ref "SV7") (pin "3") (pinfunction "3_3") (pintype "passive"))
    )
    (net (code "81") (name "unconnected-(SV7-Pad4)") (class "Default")
      (node (ref "SV7") (pin "4") (pinfunction "4_4") (pintype "passive"))
    )
    (net (code "82") (name "unconnected-(SV9-Pad3)") (class "Default")
      (node (ref "SV9") (pin "3") (pinfunction "3_3") (pintype "passive"))
    )
    (net (code "83") (name "unconnected-(SV9-Pad4)") (class "Default")
      (node (ref "SV9") (pin "4") (pinfunction "4_4") (pintype "passive"))
    )
    (net (code "84") (name "unconnected-(SV11-Pad3)") (class "Default")
      (node (ref "SV11") (pin "3") (pinfunction "3_3") (pintype "passive"))
    )
    (net (code "85") (name "unconnected-(SV11-Pad4)") (class "Default")
      (node (ref "SV11") (pin "4") (pinfunction "4_4") (pintype "passive"))
    )
  )
)
